# muscle_schematics.net
KiCad netlist of a schematic drawn in EAGLE
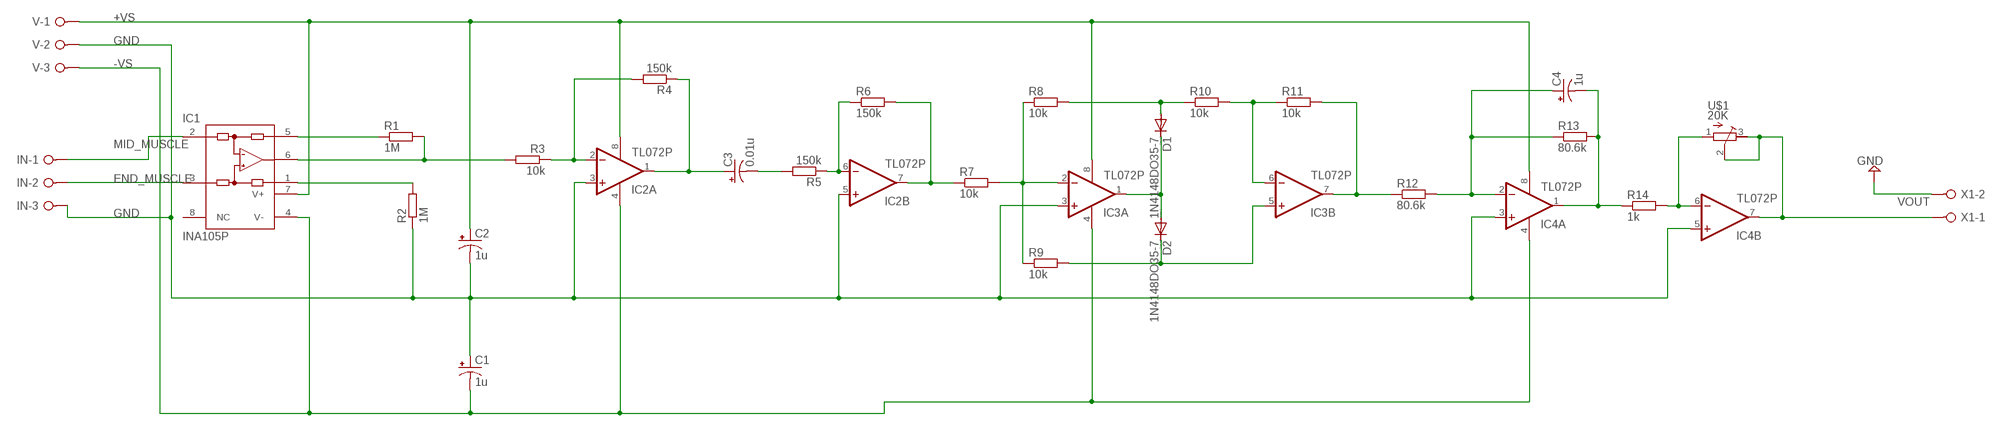
[diagram p0: schematic, sheet 1]

(export (version "E")
  (design (tool "Eeschema 10.0.6"))
  (components
    (comp (ref "C1")
      (value "1u")
      (footprint "eagle-import:E5-6")
      (libsource (lib "eagle-import") (part "CPOL-USE5-6"))
    )
    (comp (ref "C2")
      (value "1u")
      (footprint "eagle-import:E5-6")
      (libsource (lib "eagle-import") (part "CPOL-USE5-6"))
    )
    (comp (ref "C3")
      (value "0.01u")
      (footprint "eagle-import:E5-6")
      (libsource (lib "eagle-import") (part "CPOL-USE5-6"))
    )
    (comp (ref "C4")
      (value "1u")
      (footprint "eagle-import:E5-6")
      (libsource (lib "eagle-import") (part "CPOL-USE5-6"))
    )
    (comp (ref "D1")
      (value "1N4148DO35-7")
      (footprint "eagle-import:DO35-7")
      (libsource (lib "eagle-import") (part "1N4148DO35-7"))
    )
    (comp (ref "D2")
      (value "1N4148DO35-7")
      (footprint "eagle-import:DO35-7")
      (libsource (lib "eagle-import") (part "1N4148DO35-7"))
    )
    (comp (ref "IC1")
      (value "INA105P")
      (footprint "eagle-import:DIL08")
      (fields (field (name "MF") "TEXAS INSTRUMENTS") (field (name "MPN") "INA105KP"))
      (libsource (lib "eagle-import") (part "INA105P"))
    )
    (comp (ref "IC2")
      (value "TL072P")
      (footprint "eagle-import:DIL08")
      (libsource (lib "eagle-import") (part "TL072P"))
    )
    (comp (ref "IC3")
      (value "TL072P")
      (footprint "eagle-import:DIL08")
      (libsource (lib "eagle-import") (part "TL072P"))
    )
    (comp (ref "IC4")
      (value "TL072P")
      (footprint "eagle-import:DIL08")
      (libsource (lib "eagle-import") (part "TL072P"))
    )
    (comp (ref "IN")
      (value "W237-3E")
      (footprint "eagle-import:W237-3E")
      (libsource (lib "eagle-import") (part "W237-3E"))
    )
    (comp (ref "R1")
      (value "1M")
      (footprint "eagle-import:0207_10")
      (libsource (lib "eagle-import") (part "R-EU_0207/10"))
    )
    (comp (ref "R2")
      (value "1M")
      (footprint "eagle-import:0207_10")
      (libsource (lib "eagle-import") (part "R-EU_0207/10"))
    )
    (comp (ref "R3")
      (value "10k")
      (footprint "eagle-import:0207_10")
      (libsource (lib "eagle-import") (part "R-EU_0207/10"))
    )
    (comp (ref "R4")
      (value "150k")
      (footprint "eagle-import:0207_10")
      (libsource (lib "eagle-import") (part "R-EU_0207/10"))
    )
    (comp (ref "R5")
      (value "150k")
      (footprint "eagle-import:0207_10")
      (libsource (lib "eagle-import") (part "R-EU_0207/10"))
    )
    (comp (ref "R6")
      (value "150k")
      (footprint "eagle-import:0207_10")
      (libsource (lib "eagle-import") (part "R-EU_0207/10"))
    )
    (comp (ref "R7")
      (value "10k")
      (footprint "eagle-import:0207_10")
      (libsource (lib "eagle-import") (part "R-EU_0207/10"))
    )
    (comp (ref "R8")
      (value "10k")
      (footprint "eagle-import:0207_10")
      (libsource (lib "eagle-import") (part "R-EU_0207/10"))
    )
    (comp (ref "R9")
      (value "10k")
      (footprint "eagle-import:0207_10")
      (libsource (lib "eagle-import") (part "R-EU_0207/10"))
    )
    (comp (ref "R10")
      (value "10k")
      (footprint "eagle-import:0207_10")
      (libsource (lib "eagle-import") (part "R-EU_0207/10"))
    )
    (comp (ref "R11")
      (value "10k")
      (footprint "eagle-import:0207_10")
      (libsource (lib "eagle-import") (part "R-EU_0207/10"))
    )
    (comp (ref "R12")
      (value "80.6k")
      (footprint "eagle-import:0207_10")
      (libsource (lib "eagle-import") (part "R-EU_0207/10"))
    )
    (comp (ref "R13")
      (value "80.6k")
      (footprint "eagle-import:0207_10")
      (libsource (lib "eagle-import") (part "R-EU_0207/10"))
    )
    (comp (ref "R14")
      (value "1k")
      (footprint "eagle-import:0207_10")
      (libsource (lib "eagle-import") (part "R-EU_0207/10"))
    )
    (comp (ref "U$1")
      (value "20K")
      (footprint "eagle-import:RTRIM3339P")
      (libsource (lib "eagle-import") (part "R-TRIMM3339P"))
    )
    (comp (ref "V")
      (value "W237-3E")
      (footprint "eagle-import:W237-3E")
      (libsource (lib "eagle-import") (part "W237-3E"))
    )
    (comp (ref "X1")
      (value "W237-02P")
      (footprint "eagle-import:W237-132")
      (libsource (lib "eagle-import") (part "W237-02P"))
    )
  )
  (nets
    (net (code "1") (name "/+VS") (class "Default")
      (node (ref "C2") (pin "+") (pinfunction "+_+") (pintype "passive"))
      (node (ref "IC1") (pin "7") (pinfunction "V+_7") (pintype "power_in"))
      (node (ref "IC2") (pin "8") (pinfunction "V+_8") (pintype "power_in"))
      (node (ref "IC3") (pin "8") (pinfunction "V+_8") (pintype "power_in"))
      (node (ref "IC4") (pin "8") (pinfunction "V+_8") (pintype "power_in"))
      (node (ref "V") (pin "1") (pinfunction "KL_1") (pintype "passive"))
    )
    (net (code "2") (name "/-VS") (class "Default")
      (node (ref "C1") (pin "-") (pinfunction "-_-") (pintype "passive"))
      (node (ref "IC1") (pin "4") (pinfunction "V-_4") (pintype "power_in"))
      (node (ref "IC2") (pin "4") (pinfunction "V-_4") (pintype "power_in"))
      (node (ref "IC3") (pin "4") (pinfunction "V-_4") (pintype "power_in"))
      (node (ref "IC4") (pin "4") (pinfunction "V-_4") (pintype "power_in"))
      (node (ref "V") (pin "3") (pinfunction "KL_3") (pintype "passive"))
    )
    (net (code "3") (name "/END_MUSCLE") (class "Default")
      (node (ref "IC1") (pin "3") (pinfunction "+IN_3") (pintype "input"))
      (node (ref "IN") (pin "2") (pinfunction "KL_2") (pintype "passive"))
    )
    (net (code "4") (name "/MID_MUSCLE") (class "Default")
      (node (ref "IC1") (pin "2") (pinfunction "-IN_2") (pintype "input"))
      (node (ref "IN") (pin "1") (pinfunction "KL_1") (pintype "passive"))
    )
    (net (code "5") (name "/VOUT") (class "Default")
      (node (ref "IC4") (pin "7") (pinfunction "OUT_7") (pintype "output"))
      (node (ref "U$1") (pin "2") (pinfunction "S_2") (pintype "passive"))
      (node (ref "U$1") (pin "3") (pinfunction "E_3") (pintype "passive"))
      (node (ref "X1") (pin "1") (pinfunction "KL_1") (pintype "passive"))
    )
    (net (code "6") (name "GND") (class "Default")
      (node (ref "C1") (pin "+") (pinfunction "+_+") (pintype "passive"))
      (node (ref "C2") (pin "-") (pinfunction "-_-") (pintype "passive"))
      (node (ref "IC2") (pin "3") (pinfunction "+IN_3") (pintype "input"))
      (node (ref "IC2") (pin "5") (pinfunction "+IN_5") (pintype "input"))
      (node (ref "IC3") (pin "3") (pinfunction "+IN_3") (pintype "input"))
      (node (ref "IC4") (pin "3") (pinfunction "+IN_3") (pintype "input"))
      (node (ref "IC4") (pin "5") (pinfunction "+IN_5") (pintype "input"))
      (node (ref "IN") (pin "3") (pinfunction "KL_3") (pintype "passive"))
      (node (ref "R2") (pin "1") (pinfunction "1_1") (pintype "passive"))
      (node (ref "V") (pin "2") (pinfunction "KL_2") (pintype "passive"))
      (node (ref "X1") (pin "2") (pinfunction "KL_2") (pintype "passive"))
    )
    (net (code "7") (name "Net-(C3-Pad-)") (class "Default")
      (node (ref "C3") (pin "-") (pinfunction "-_-") (pintype "passive"))
      (node (ref "R5") (pin "2") (pinfunction "2_2") (pintype "passive"))
    )
    (net (code "8") (name "Net-(D1-PadA)") (class "Default")
      (node (ref "D1") (pin "A") (pinfunction "A_A") (pintype "passive"))
      (node (ref "R10") (pin "1") (pinfunction "1_1") (pintype "passive"))
      (node (ref "R8") (pin "2") (pinfunction "2_2") (pintype "passive"))
    )
    (net (code "9") (name "Net-(IC1-OUT)") (class "Default")
      (node (ref "IC1") (pin "6") (pinfunction "OUT_6") (pintype "output"))
      (node (ref "R1") (pin "2") (pinfunction "2_2") (pintype "passive"))
      (node (ref "R3") (pin "2") (pinfunction "2_2") (pintype "passive"))
    )
    (net (code "10") (name "Net-(IC1-REF)") (class "Default")
      (node (ref "IC1") (pin "1") (pinfunction "REF_1") (pintype "passive"))
      (node (ref "R2") (pin "2") (pinfunction "2_2") (pintype "passive"))
    )
    (net (code "11") (name "Net-(IC1-SENSE)") (class "Default")
      (node (ref "IC1") (pin "5") (pinfunction "SENSE_5") (pintype "passive"))
      (node (ref "R1") (pin "1") (pinfunction "1_1") (pintype "passive"))
    )
    (net (code "12") (name "Net-(IC2A--IN)") (class "Default")
      (node (ref "IC2") (pin "2") (pinfunction "-IN_2") (pintype "input"))
      (node (ref "R3") (pin "1") (pinfunction "1_1") (pintype "passive"))
      (node (ref "R4") (pin "2") (pinfunction "2_2") (pintype "passive"))
    )
    (net (code "13") (name "Net-(IC2A-OUT)") (class "Default")
      (node (ref "C3") (pin "+") (pinfunction "+_+") (pintype "passive"))
      (node (ref "IC2") (pin "1") (pinfunction "OUT_1") (pintype "output"))
      (node (ref "R4") (pin "1") (pinfunction "1_1") (pintype "passive"))
    )
    (net (code "14") (name "Net-(IC2B--IN)") (class "Default")
      (node (ref "IC2") (pin "6") (pinfunction "-IN_6") (pintype "input"))
      (node (ref "R5") (pin "1") (pinfunction "1_1") (pintype "passive"))
      (node (ref "R6") (pin "1") (pinfunction "1_1") (pintype "passive"))
    )
    (net (code "15") (name "Net-(IC2B-OUT)") (class "Default")
      (node (ref "IC2") (pin "7") (pinfunction "OUT_7") (pintype "output"))
      (node (ref "R6") (pin "2") (pinfunction "2_2") (pintype "passive"))
      (node (ref "R7") (pin "1") (pinfunction "1_1") (pintype "passive"))
    )
    (net (code "16") (name "Net-(IC3A--IN)") (class "Default")
      (node (ref "IC3") (pin "2") (pinfunction "-IN_2") (pintype "input"))
      (node (ref "R7") (pin "2") (pinfunction "2_2") (pintype "passive"))
      (node (ref "R8") (pin "1") (pinfunction "1_1") (pintype "passive"))
      (node (ref "R9") (pin "1") (pinfunction "1_1") (pintype "passive"))
    )
    (net (code "17") (name "Net-(IC3A-OUT)") (class "Default")
      (node (ref "D1") (pin "C") (pinfunction "C_C") (pintype "passive"))
      (node (ref "D2") (pin "A") (pinfunction "A_A") (pintype "passive"))
      (node (ref "IC3") (pin "1") (pinfunction "OUT_1") (pintype "output"))
    )
    (net (code "18") (name "Net-(IC3B-+IN)") (class "Default")
      (node (ref "D2") (pin "C") (pinfunction "C_C") (pintype "passive"))
      (node (ref "IC3") (pin "5") (pinfunction "+IN_5") (pintype "input"))
      (node (ref "R9") (pin "2") (pinfunction "2_2") (pintype "passive"))
    )
    (net (code "19") (name "Net-(IC3B--IN)") (class "Default")
      (node (ref "IC3") (pin "6") (pinfunction "-IN_6") (pintype "input"))
      (node (ref "R10") (pin "2") (pinfunction "2_2") (pintype "passive"))
      (node (ref "R11") (pin "1") (pinfunction "1_1") (pintype "passive"))
    )
    (net (code "20") (name "Net-(IC3B-OUT)") (class "Default")
      (node (ref "IC3") (pin "7") (pinfunction "OUT_7") (pintype "output"))
      (node (ref "R11") (pin "2") (pinfunction "2_2") (pintype "passive"))
      (node (ref "R12") (pin "1") (pinfunction "1_1") (pintype "passive"))
    )
    (net (code "21") (name "Net-(IC4A--IN)") (class "Default")
      (node (ref "C4") (pin "+") (pinfunction "+_+") (pintype "passive"))
      (node (ref "IC4") (pin "2") (pinfunction "-IN_2") (pintype "input"))
      (node (ref "R12") (pin "2") (pinfunction "2_2") (pintype "passive"))
      (node (ref "R13") (pin "1") (pinfunction "1_1") (pintype "passive"))
    )
    (net (code "22") (name "Net-(IC4A-OUT)") (class "Default")
      (node (ref "C4") (pin "-") (pinfunction "-_-") (pintype "passive"))
      (node (ref "IC4") (pin "1") (pinfunction "OUT_1") (pintype "output"))
      (node (ref "R13") (pin "2") (pinfunction "2_2") (pintype "passive"))
      (node (ref "R14") (pin "1") (pinfunction "1_1") (pintype "passive"))
    )
    (net (code "23") (name "Net-(IC4B--IN)") (class "Default")
      (node (ref "IC4") (pin "6") (pinfunction "-IN_6") (pintype "input"))
      (node (ref "R14") (pin "2") (pinfunction "2_2") (pintype "passive"))
      (node (ref "U$1") (pin "1") (pinfunction "A_1") (pintype "passive"))
    )
    (net (code "24") (name "unconnected-(IC1-NC-Pad8)") (class "Default")
      (node (ref "IC1") (pin "8") (pinfunction "NC_8") (pintype "no_connect"))
    )
  )
)
